# drv8353_based_bldc_power_stage.net
KiCad netlist of a schematic drawn in EAGLE
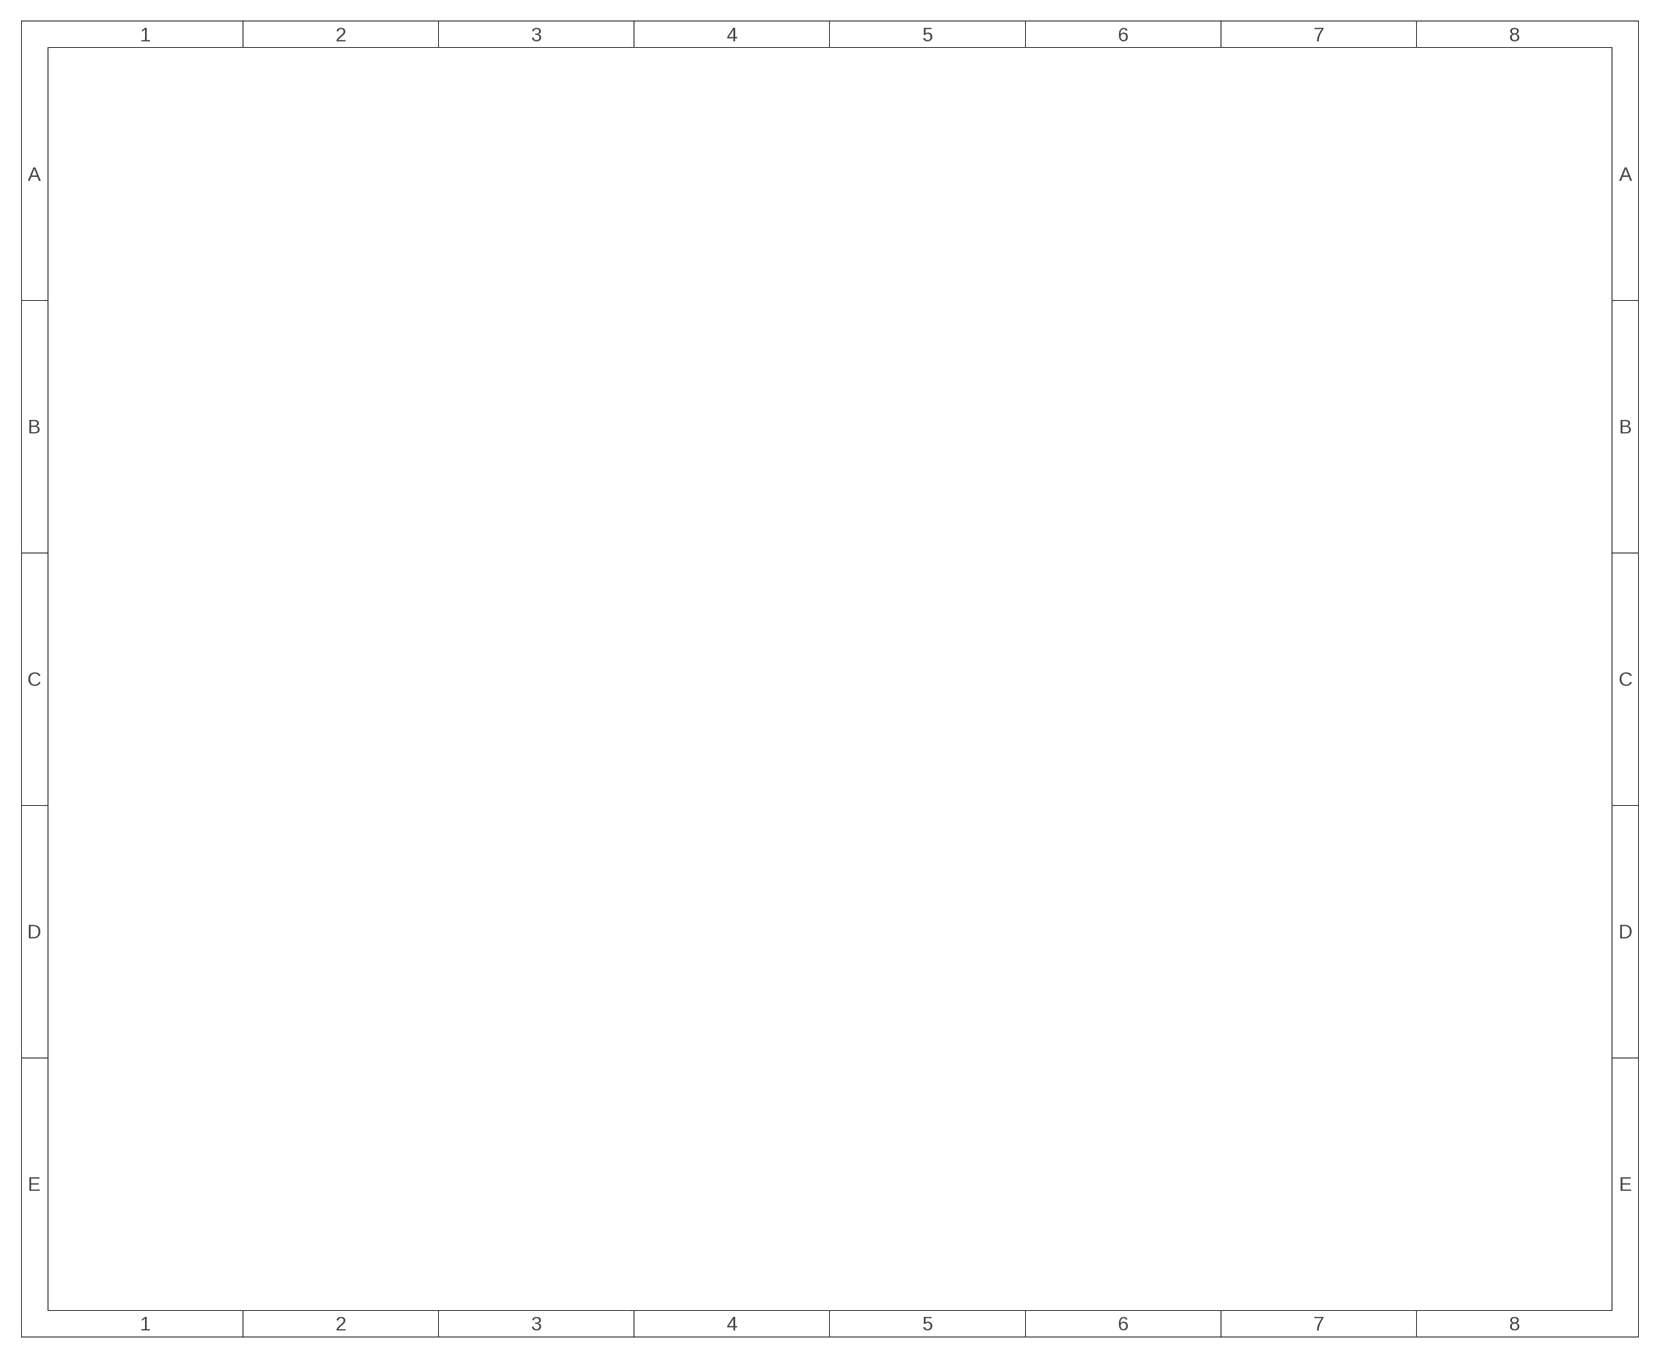
[diagram p0: schematic, sheet 1]
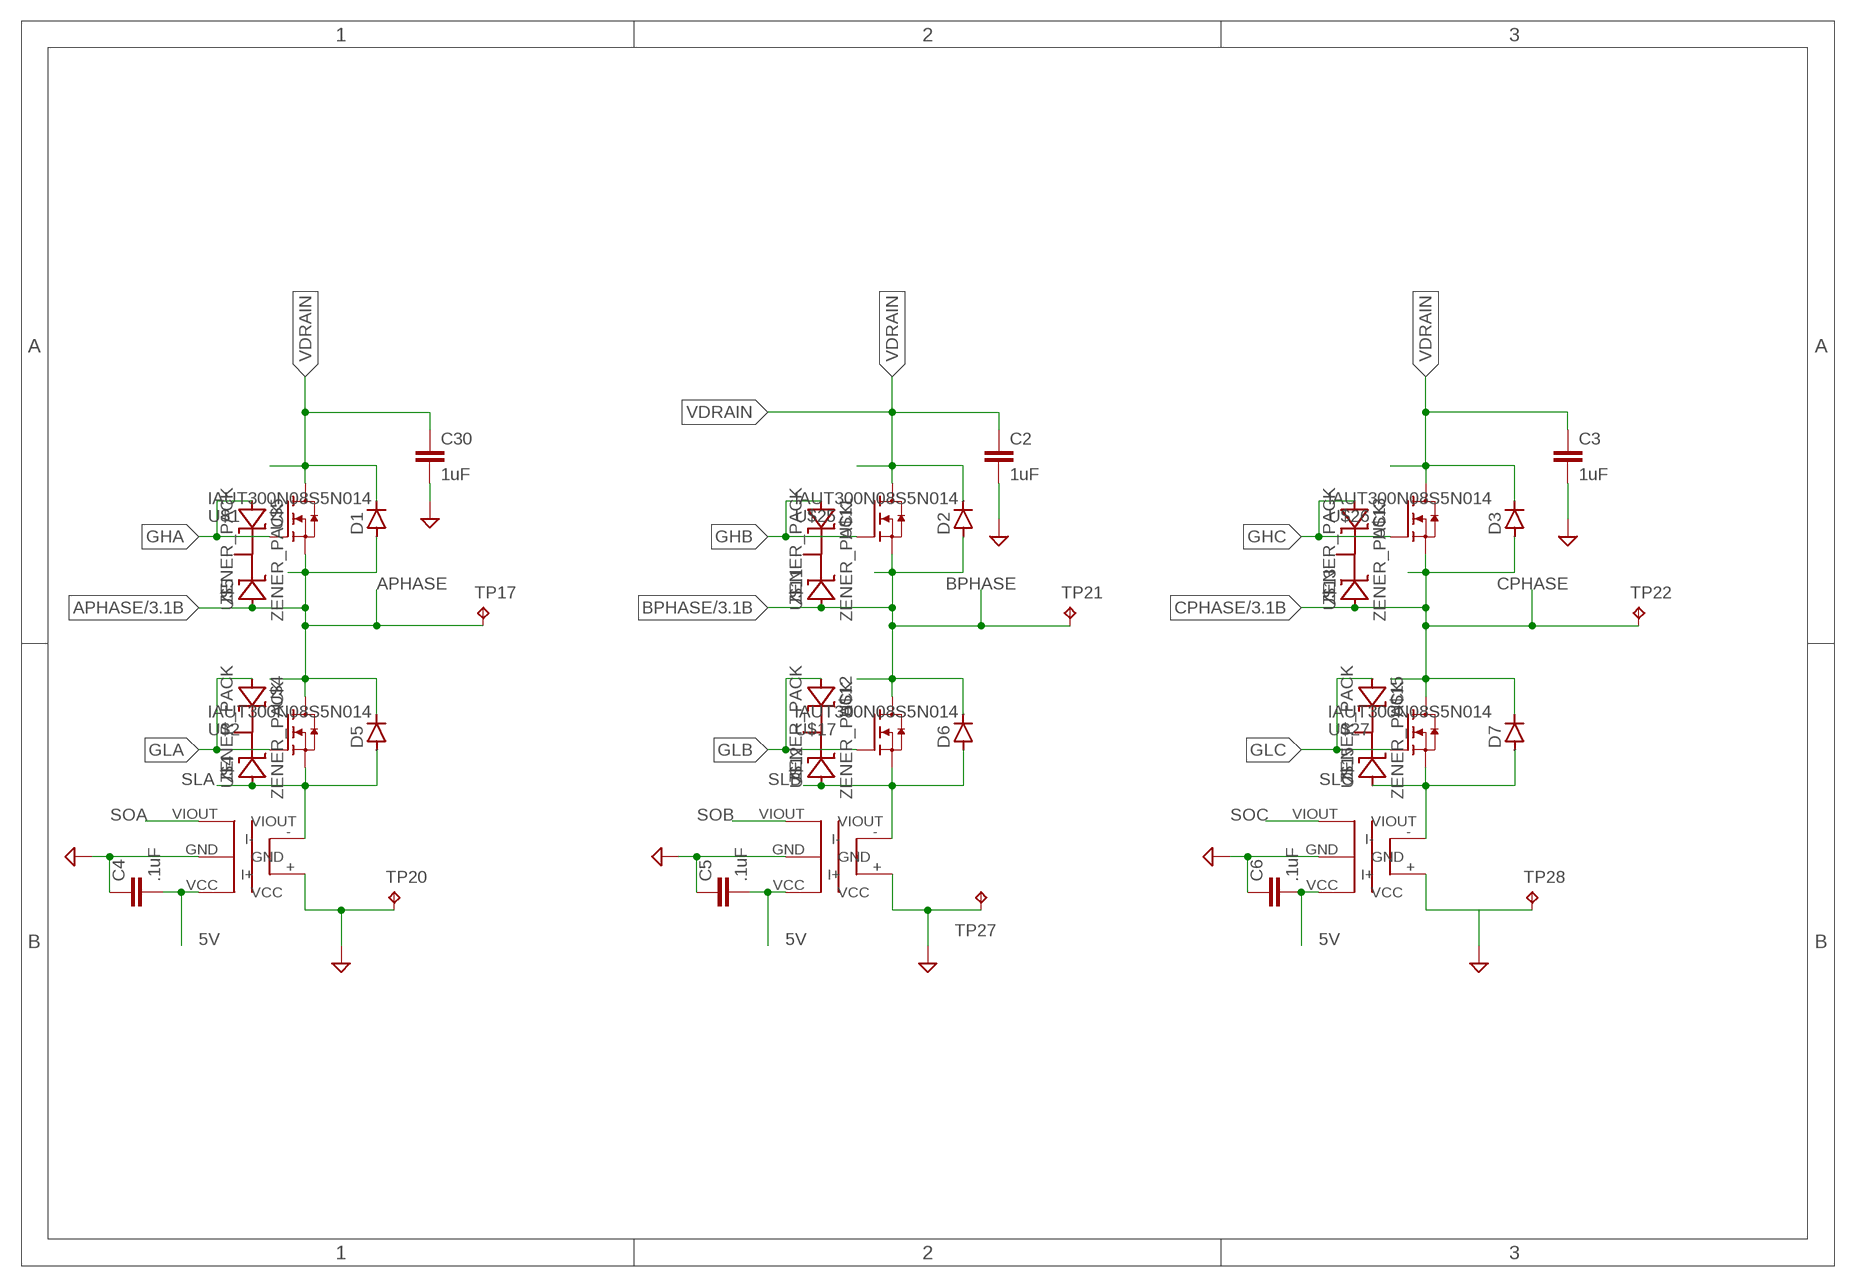
[diagram p1: schematic, sheet 2]
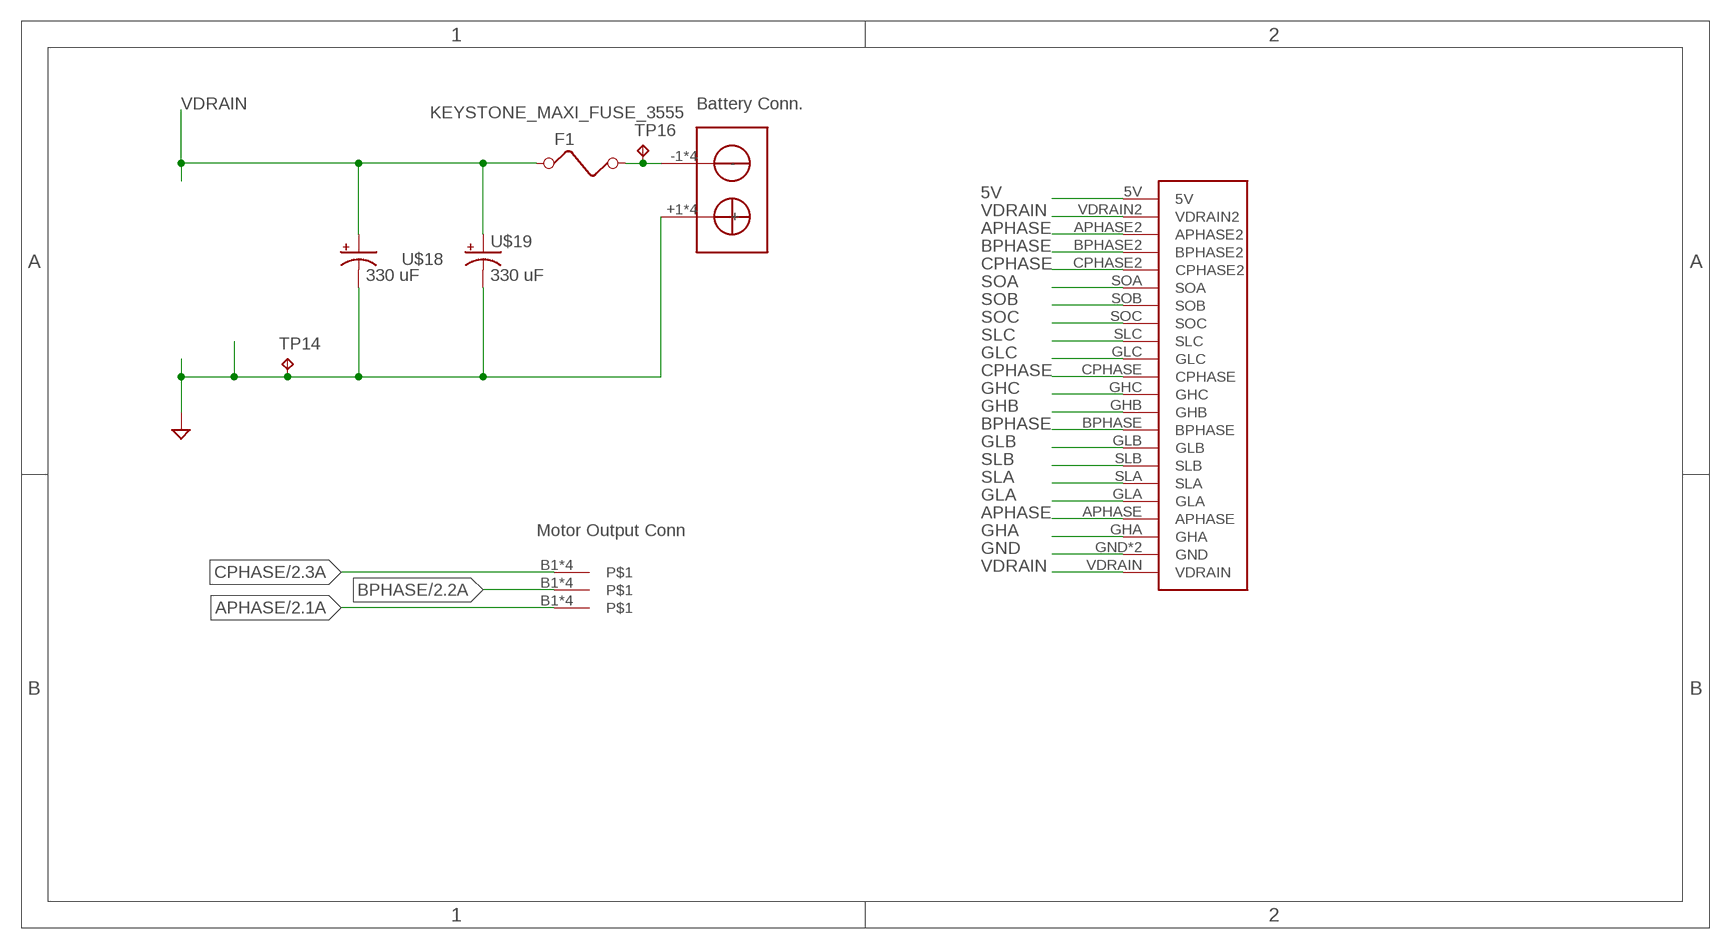
[diagram p2: schematic, sheet 3]

(export (version "E")
  (design (tool "Eeschema 10.0.6"))
  (components
    (comp (ref "C2")
      (value "1uF")
      (footprint "eagle-import:C1206")
      (libsource (lib "eagle-import") (part "C-EUC1206"))
    )
    (comp (ref "C3")
      (value "1uF")
      (footprint "eagle-import:C1206")
      (libsource (lib "eagle-import") (part "C-EUC1206"))
    )
    (comp (ref "C4")
      (value ".1uF")
      (footprint "eagle-import:C0603K")
      (libsource (lib "eagle-import") (part "C-EUC0603K"))
    )
    (comp (ref "C5")
      (value ".1uF")
      (footprint "eagle-import:C0603K")
      (libsource (lib "eagle-import") (part "C-EUC0603K"))
    )
    (comp (ref "C6")
      (value ".1uF")
      (footprint "eagle-import:C0603K")
      (libsource (lib "eagle-import") (part "C-EUC0603K"))
    )
    (comp (ref "C30")
      (value "1uF")
      (footprint "eagle-import:C1206")
      (libsource (lib "eagle-import") (part "C-EUC1206"))
    )
    (comp (ref "D1")
      (value "D-SOD123")
      (footprint "eagle-import:SOD123")
      (libsource (lib "eagle-import") (part "D-SOD123"))
    )
    (comp (ref "D2")
      (value "D-SOD123")
      (footprint "eagle-import:SOD123")
      (libsource (lib "eagle-import") (part "D-SOD123"))
    )
    (comp (ref "D3")
      (value "D-SOD123")
      (footprint "eagle-import:SOD123")
      (libsource (lib "eagle-import") (part "D-SOD123"))
    )
    (comp (ref "D5")
      (value "D-SOD123")
      (footprint "eagle-import:SOD123")
      (libsource (lib "eagle-import") (part "D-SOD123"))
    )
    (comp (ref "D6")
      (value "D-SOD123")
      (footprint "eagle-import:SOD123")
      (libsource (lib "eagle-import") (part "D-SOD123"))
    )
    (comp (ref "D7")
      (value "D-SOD123")
      (footprint "eagle-import:SOD123")
      (libsource (lib "eagle-import") (part "D-SOD123"))
    )
    (comp (ref "TP17")
      (value "TPB1,27")
      (footprint "eagle-import:B1,27")
      (libsource (lib "eagle-import") (part "TPB1,27"))
    )
    (comp (ref "TP20")
      (value "TPB1,27")
      (footprint "eagle-import:B1,27")
      (libsource (lib "eagle-import") (part "TPB1,27"))
    )
    (comp (ref "TP21")
      (value "TPB1,27")
      (footprint "eagle-import:B1,27")
      (libsource (lib "eagle-import") (part "TPB1,27"))
    )
    (comp (ref "TP22")
      (value "TPB1,27")
      (footprint "eagle-import:B1,27")
      (libsource (lib "eagle-import") (part "TPB1,27"))
    )
    (comp (ref "TP27")
      (value "TPB1,27")
      (footprint "eagle-import:B1,27")
      (libsource (lib "eagle-import") (part "TPB1,27"))
    )
    (comp (ref "TP28")
      (value "TPB1,27")
      (footprint "eagle-import:B1,27")
      (libsource (lib "eagle-import") (part "TPB1,27"))
    )
    (comp (ref "U$1")
      (value "IAUT300N08S5N014")
      (footprint "eagle-import:PG-HSOF-8-1_MODIFIED")
      (libsource (lib "eagle-import") (part "IAUT300N08S5N014"))
    )
    (comp (ref "U$2")
      (value "IAUT300N08S5N014")
      (footprint "eagle-import:PG-HSOF-8-1_MODIFIED")
      (libsource (lib "eagle-import") (part "IAUT300N08S5N014"))
    )
    (comp (ref "U$3")
      (value "ACS770LCB-050B-PFF-T")
      (footprint "eagle-import:LEADFORM_PFF")
      (libsource (lib "eagle-import") (part "ACS770LCB-050B-PFF-T"))
    )
    (comp (ref "U$4")
      (value "ZENER_PACK")
      (footprint "eagle-import:SOT23")
      (libsource (lib "eagle-import") (part "ZENER_PACK"))
    )
    (comp (ref "U$5")
      (value "ZENER_PACK")
      (footprint "eagle-import:SOT23")
      (libsource (lib "eagle-import") (part "ZENER_PACK"))
    )
    (comp (ref "U$9")
      (value "ACS770LCB-050B-PFF-T")
      (footprint "eagle-import:LEADFORM_PFF")
      (libsource (lib "eagle-import") (part "ACS770LCB-050B-PFF-T"))
    )
    (comp (ref "U$10")
      (value "ACS770LCB-050B-PFF-T")
      (footprint "eagle-import:LEADFORM_PFF")
      (libsource (lib "eagle-import") (part "ACS770LCB-050B-PFF-T"))
    )
    (comp (ref "U$11")
      (value "ZENER_PACK")
      (footprint "eagle-import:SOT23")
      (libsource (lib "eagle-import") (part "ZENER_PACK"))
    )
    (comp (ref "U$12")
      (value "ZENER_PACK")
      (footprint "eagle-import:SOT23")
      (libsource (lib "eagle-import") (part "ZENER_PACK"))
    )
    (comp (ref "U$13")
      (value "ZENER_PACK")
      (footprint "eagle-import:SOT23")
      (libsource (lib "eagle-import") (part "ZENER_PACK"))
    )
    (comp (ref "U$15")
      (value "ZENER_PACK")
      (footprint "eagle-import:SOT23")
      (libsource (lib "eagle-import") (part "ZENER_PACK"))
    )
    (comp (ref "U$17")
      (value "IAUT300N08S5N014")
      (footprint "eagle-import:PG-HSOF-8-1_MODIFIED")
      (libsource (lib "eagle-import") (part "IAUT300N08S5N014"))
    )
    (comp (ref "U$25")
      (value "IAUT300N08S5N014")
      (footprint "eagle-import:PG-HSOF-8-1_MODIFIED")
      (libsource (lib "eagle-import") (part "IAUT300N08S5N014"))
    )
    (comp (ref "U$26")
      (value "IAUT300N08S5N014")
      (footprint "eagle-import:PG-HSOF-8-1_MODIFIED")
      (libsource (lib "eagle-import") (part "IAUT300N08S5N014"))
    )
    (comp (ref "U$27")
      (value "IAUT300N08S5N014")
      (footprint "eagle-import:PG-HSOF-8-1_MODIFIED")
      (libsource (lib "eagle-import") (part "IAUT300N08S5N014"))
    )
    (comp (ref "F1")
      (value "KEYSTONE_MAXI_FUSE_3555")
      (footprint "eagle-import:KEYSTONE_MAXI_FUSE_CLIP_3555")
      (libsource (lib "eagle-import") (part "KEYSTONE_MAXI_FUSE_3555"))
    )
    (comp (ref "TP14")
      (value "TPB1,27")
      (footprint "eagle-import:B1,27")
      (libsource (lib "eagle-import") (part "TPB1,27"))
    )
    (comp (ref "TP16")
      (value "TPB1,27")
      (footprint "eagle-import:B1,27")
      (libsource (lib "eagle-import") (part "TPB1,27"))
    )
    (comp (ref "U$6")
      (value "MINI-PP75")
      (footprint "eagle-import:MINI-PP75")
      (libsource (lib "eagle-import") (part "MINI-PP75"))
    )
    (comp (ref "U$7")
      (value "MINI-PP75")
      (footprint "eagle-import:MINI-PP75")
      (libsource (lib "eagle-import") (part "MINI-PP75"))
    )
    (comp (ref "U$8")
      (value "MINI-PP75")
      (footprint "eagle-import:MINI-PP75")
      (libsource (lib "eagle-import") (part "MINI-PP75"))
    )
    (comp (ref "U$14")
      (value "POWER_STAGE_CONNECTOR")
      (footprint "eagle-import:POWER_STAGE_CONNECTION")
      (libsource (lib "eagle-import") (part "POWER_STAGE_CONNECTOR"))
    )
    (comp (ref "U$16")
      (value "SB50")
      (footprint "eagle-import:MINI-SB-50")
      (libsource (lib "eagle-import") (part "SB50"))
    )
    (comp (ref "U$18")
      (value "330 uF")
      (footprint "eagle-import:SM_RADIAL_K16_1PRIMARY")
      (libsource (lib "eagle-import") (part "RADIALK16"))
    )
    (comp (ref "U$19")
      (value "330 uF")
      (footprint "eagle-import:SM_RADIAL_K16_1PRIMARY")
      (libsource (lib "eagle-import") (part "RADIALK16"))
    )
  )
  (nets
    (net (code "1") (name "5V") (class "Default")
      (node (ref "C4") (pin "2") (pinfunction "2_2") (pintype "passive"))
      (node (ref "C5") (pin "2") (pinfunction "2_2") (pintype "passive"))
      (node (ref "C6") (pin "2") (pinfunction "2_2") (pintype "passive"))
      (node (ref "U$10") (pin "VCC") (pinfunction "VCC_VCC") (pintype "bidirectional"))
      (node (ref "U$14") (pin "5V") (pinfunction "5V_5V") (pintype "bidirectional"))
      (node (ref "U$3") (pin "VCC") (pinfunction "VCC_VCC") (pintype "bidirectional"))
      (node (ref "U$9") (pin "VCC") (pinfunction "VCC_VCC") (pintype "bidirectional"))
    )
    (net (code "2") (name "APHASE") (class "Default")
      (node (ref "D1") (pin "2") (pinfunction "A_2") (pintype "passive"))
      (node (ref "D5") (pin "LINE") (pinfunction "C_LINE") (pintype "passive"))
      (node (ref "TP17") (pin "TP") (pinfunction "TP_TP") (pintype "input"))
      (node (ref "U$1") (pin "10") (pinfunction "S_10") (pintype "passive"))
      (node (ref "U$1") (pin "11") (pinfunction "S_11") (pintype "passive"))
      (node (ref "U$1") (pin "12") (pinfunction "S_12") (pintype "passive"))
      (node (ref "U$1") (pin "13") (pinfunction "S_13") (pintype "passive"))
      (node (ref "U$1") (pin "14") (pinfunction "S_14") (pintype "passive"))
      (node (ref "U$1") (pin "15") (pinfunction "S_15") (pintype "passive"))
      (node (ref "U$1") (pin "2") (pinfunction "S_2") (pintype "passive"))
      (node (ref "U$1") (pin "3") (pinfunction "S_3") (pintype "passive"))
      (node (ref "U$1") (pin "4") (pinfunction "S_4") (pintype "passive"))
      (node (ref "U$1") (pin "5") (pinfunction "S_5") (pintype "passive"))
      (node (ref "U$1") (pin "6") (pinfunction "S_6") (pintype "passive"))
      (node (ref "U$1") (pin "7") (pinfunction "S_7") (pintype "passive"))
      (node (ref "U$1") (pin "8") (pinfunction "S_8") (pintype "passive"))
      (node (ref "U$14") (pin "APHASE") (pinfunction "APHASE_APHASE") (pintype "bidirectional"))
      (node (ref "U$14") (pin "APHASE2") (pinfunction "APHASE2_APHASE2") (pintype "bidirectional"))
      (node (ref "U$2") (pin "16") (pinfunction "D_16") (pintype "passive"))
      (node (ref "U$2") (pin "17") (pinfunction "D_17") (pintype "passive"))
      (node (ref "U$2") (pin "18") (pinfunction "D_18") (pintype "passive"))
      (node (ref "U$2") (pin "19") (pinfunction "D_19") (pintype "passive"))
      (node (ref "U$2") (pin "9") (pinfunction "D_9") (pintype "passive"))
      (node (ref "U$5") (pin "1") (pinfunction "END1_1") (pintype "passive"))
      (node (ref "U$8") (pin "B1") (pinfunction "P$1_B1") (pintype "bidirectional"))
      (node (ref "U$8") (pin "B2") (pinfunction "P$1_B2") (pintype "bidirectional"))
      (node (ref "U$8") (pin "B3") (pinfunction "P$1_B3") (pintype "bidirectional"))
      (node (ref "U$8") (pin "B4") (pinfunction "P$1_B4") (pintype "bidirectional"))
    )
    (net (code "3") (name "BPHASE") (class "Default")
      (node (ref "D2") (pin "2") (pinfunction "A_2") (pintype "passive"))
      (node (ref "D6") (pin "LINE") (pinfunction "C_LINE") (pintype "passive"))
      (node (ref "TP21") (pin "TP") (pinfunction "TP_TP") (pintype "input"))
      (node (ref "U$11") (pin "1") (pinfunction "END1_1") (pintype "passive"))
      (node (ref "U$14") (pin "BPHASE") (pinfunction "BPHASE_BPHASE") (pintype "bidirectional"))
      (node (ref "U$14") (pin "BPHASE2") (pinfunction "BPHASE2_BPHASE2") (pintype "bidirectional"))
      (node (ref "U$17") (pin "16") (pinfunction "D_16") (pintype "passive"))
      (node (ref "U$17") (pin "17") (pinfunction "D_17") (pintype "passive"))
      (node (ref "U$17") (pin "18") (pinfunction "D_18") (pintype "passive"))
      (node (ref "U$17") (pin "19") (pinfunction "D_19") (pintype "passive"))
      (node (ref "U$17") (pin "9") (pinfunction "D_9") (pintype "passive"))
      (node (ref "U$25") (pin "10") (pinfunction "S_10") (pintype "passive"))
      (node (ref "U$25") (pin "11") (pinfunction "S_11") (pintype "passive"))
      (node (ref "U$25") (pin "12") (pinfunction "S_12") (pintype "passive"))
      (node (ref "U$25") (pin "13") (pinfunction "S_13") (pintype "passive"))
      (node (ref "U$25") (pin "14") (pinfunction "S_14") (pintype "passive"))
      (node (ref "U$25") (pin "15") (pinfunction "S_15") (pintype "passive"))
      (node (ref "U$25") (pin "2") (pinfunction "S_2") (pintype "passive"))
      (node (ref "U$25") (pin "3") (pinfunction "S_3") (pintype "passive"))
      (node (ref "U$25") (pin "4") (pinfunction "S_4") (pintype "passive"))
      (node (ref "U$25") (pin "5") (pinfunction "S_5") (pintype "passive"))
      (node (ref "U$25") (pin "6") (pinfunction "S_6") (pintype "passive"))
      (node (ref "U$25") (pin "7") (pinfunction "S_7") (pintype "passive"))
      (node (ref "U$25") (pin "8") (pinfunction "S_8") (pintype "passive"))
      (node (ref "U$7") (pin "B1") (pinfunction "P$1_B1") (pintype "bidirectional"))
      (node (ref "U$7") (pin "B2") (pinfunction "P$1_B2") (pintype "bidirectional"))
      (node (ref "U$7") (pin "B3") (pinfunction "P$1_B3") (pintype "bidirectional"))
      (node (ref "U$7") (pin "B4") (pinfunction "P$1_B4") (pintype "bidirectional"))
    )
    (net (code "4") (name "CPHASE") (class "Default")
      (node (ref "D3") (pin "2") (pinfunction "A_2") (pintype "passive"))
      (node (ref "D7") (pin "LINE") (pinfunction "C_LINE") (pintype "passive"))
      (node (ref "TP22") (pin "TP") (pinfunction "TP_TP") (pintype "input"))
      (node (ref "U$13") (pin "1") (pinfunction "END1_1") (pintype "passive"))
      (node (ref "U$14") (pin "CPHASE") (pinfunction "CPHASE_CPHASE") (pintype "bidirectional"))
      (node (ref "U$14") (pin "CPHASE2") (pinfunction "CPHASE2_CPHASE2") (pintype "bidirectional"))
      (node (ref "U$26") (pin "10") (pinfunction "S_10") (pintype "passive"))
      (node (ref "U$26") (pin "11") (pinfunction "S_11") (pintype "passive"))
      (node (ref "U$26") (pin "12") (pinfunction "S_12") (pintype "passive"))
      (node (ref "U$26") (pin "13") (pinfunction "S_13") (pintype "passive"))
      (node (ref "U$26") (pin "14") (pinfunction "S_14") (pintype "passive"))
      (node (ref "U$26") (pin "15") (pinfunction "S_15") (pintype "passive"))
      (node (ref "U$26") (pin "2") (pinfunction "S_2") (pintype "passive"))
      (node (ref "U$26") (pin "3") (pinfunction "S_3") (pintype "passive"))
      (node (ref "U$26") (pin "4") (pinfunction "S_4") (pintype "passive"))
      (node (ref "U$26") (pin "5") (pinfunction "S_5") (pintype "passive"))
      (node (ref "U$26") (pin "6") (pinfunction "S_6") (pintype "passive"))
      (node (ref "U$26") (pin "7") (pinfunction "S_7") (pintype "passive"))
      (node (ref "U$26") (pin "8") (pinfunction "S_8") (pintype "passive"))
      (node (ref "U$27") (pin "16") (pinfunction "D_16") (pintype "passive"))
      (node (ref "U$27") (pin "17") (pinfunction "D_17") (pintype "passive"))
      (node (ref "U$27") (pin "18") (pinfunction "D_18") (pintype "passive"))
      (node (ref "U$27") (pin "19") (pinfunction "D_19") (pintype "passive"))
      (node (ref "U$27") (pin "9") (pinfunction "D_9") (pintype "passive"))
      (node (ref "U$6") (pin "B1") (pinfunction "P$1_B1") (pintype "bidirectional"))
      (node (ref "U$6") (pin "B2") (pinfunction "P$1_B2") (pintype "bidirectional"))
      (node (ref "U$6") (pin "B3") (pinfunction "P$1_B3") (pintype "bidirectional"))
      (node (ref "U$6") (pin "B4") (pinfunction "P$1_B4") (pintype "bidirectional"))
    )
    (net (code "5") (name "GHA") (class "Default")
      (node (ref "U$1") (pin "1") (pinfunction "G_1") (pintype "passive"))
      (node (ref "U$14") (pin "GHA") (pinfunction "GHA_GHA") (pintype "bidirectional"))
      (node (ref "U$5") (pin "2") (pinfunction "END2_2") (pintype "passive"))
    )
    (net (code "6") (name "GHB") (class "Default")
      (node (ref "U$11") (pin "2") (pinfunction "END2_2") (pintype "passive"))
      (node (ref "U$14") (pin "GHB") (pinfunction "GHB_GHB") (pintype "bidirectional"))
      (node (ref "U$25") (pin "1") (pinfunction "G_1") (pintype "passive"))
    )
    (net (code "7") (name "GHC") (class "Default")
      (node (ref "U$13") (pin "2") (pinfunction "END2_2") (pintype "passive"))
      (node (ref "U$14") (pin "GHC") (pinfunction "GHC_GHC") (pintype "bidirectional"))
      (node (ref "U$26") (pin "1") (pinfunction "G_1") (pintype "passive"))
    )
    (net (code "8") (name "GLA") (class "Default")
      (node (ref "U$14") (pin "GLA") (pinfunction "GLA_GLA") (pintype "bidirectional"))
      (node (ref "U$2") (pin "1") (pinfunction "G_1") (pintype "passive"))
      (node (ref "U$4") (pin "2") (pinfunction "END2_2") (pintype "passive"))
    )
    (net (code "9") (name "GLB") (class "Default")
      (node (ref "U$12") (pin "2") (pinfunction "END2_2") (pintype "passive"))
      (node (ref "U$14") (pin "GLB") (pinfunction "GLB_GLB") (pintype "bidirectional"))
      (node (ref "U$17") (pin "1") (pinfunction "G_1") (pintype "passive"))
    )
    (net (code "10") (name "GLC") (class "Default")
      (node (ref "U$14") (pin "GLC") (pinfunction "GLC_GLC") (pintype "bidirectional"))
      (node (ref "U$15") (pin "2") (pinfunction "END2_2") (pintype "passive"))
      (node (ref "U$27") (pin "1") (pinfunction "G_1") (pintype "passive"))
    )
    (net (code "11") (name "GND") (class "Default")
      (node (ref "C2") (pin "2") (pinfunction "2_2") (pintype "passive"))
      (node (ref "C3") (pin "2") (pinfunction "2_2") (pintype "passive"))
      (node (ref "C30") (pin "2") (pinfunction "2_2") (pintype "passive"))
      (node (ref "C4") (pin "1") (pinfunction "1_1") (pintype "passive"))
      (node (ref "C5") (pin "1") (pinfunction "1_1") (pintype "passive"))
      (node (ref "C6") (pin "1") (pinfunction "1_1") (pintype "passive"))
      (node (ref "TP14") (pin "TP") (pinfunction "TP_TP") (pintype "input"))
      (node (ref "TP20") (pin "TP") (pinfunction "TP_TP") (pintype "input"))
      (node (ref "TP27") (pin "TP") (pinfunction "TP_TP") (pintype "input"))
      (node (ref "TP28") (pin "TP") (pinfunction "TP_TP") (pintype "input"))
      (node (ref "U$10") (pin "+") (pinfunction "I+_+") (pintype "bidirectional"))
      (node (ref "U$10") (pin "GND") (pinfunction "GND_GND") (pintype "bidirectional"))
      (node (ref "U$14") (pin "GND") (pinfunction "GND_GND") (pintype "bidirectional"))
      (node (ref "U$14") (pin "GND2") (pinfunction "GND_GND2") (pintype "bidirectional"))
      (node (ref "U$16") (pin "+1") (pinfunction "+_+1") (pintype "bidirectional"))
      (node (ref "U$16") (pin "+2") (pinfunction "+_+2") (pintype "bidirectional"))
      (node (ref "U$16") (pin "+3") (pinfunction "+_+3") (pintype "bidirectional"))
      (node (ref "U$16") (pin "+4") (pinfunction "+_+4") (pintype "bidirectional"))
      (node (ref "U$18") (pin "-") (pinfunction "-_-") (pintype "passive"))
      (node (ref "U$19") (pin "-") (pinfunction "-_-") (pintype "passive"))
      (node (ref "U$3") (pin "+") (pinfunction "I+_+") (pintype "bidirectional"))
      (node (ref "U$3") (pin "GND") (pinfunction "GND_GND") (pintype "bidirectional"))
      (node (ref "U$9") (pin "+") (pinfunction "I+_+") (pintype "bidirectional"))
      (node (ref "U$9") (pin "GND") (pinfunction "GND_GND") (pintype "bidirectional"))
    )
    (net (code "12") (name "Net-(F1-2-PadB1)") (class "Default")
      (node (ref "F1") (pin "B1") (pinfunction "2_B1") (pintype "passive"))
      (node (ref "F1") (pin "B2") (pinfunction "2_B2") (pintype "passive"))
      (node (ref "TP16") (pin "TP") (pinfunction "TP_TP") (pintype "input"))
      (node (ref "U$16") (pin "-1") (pinfunction "-_-1") (pintype "bidirectional"))
      (node (ref "U$16") (pin "-2") (pinfunction "-_-2") (pintype "bidirectional"))
      (node (ref "U$16") (pin "-3") (pinfunction "-_-3") (pintype "bidirectional"))
      (node (ref "U$16") (pin "-4") (pinfunction "-_-4") (pintype "bidirectional"))
    )
    (net (code "13") (name "SLA") (class "Default")
      (node (ref "D5") (pin "2") (pinfunction "A_2") (pintype "passive"))
      (node (ref "U$14") (pin "SLA") (pinfunction "SLA_SLA") (pintype "bidirectional"))
      (node (ref "U$2") (pin "10") (pinfunction "S_10") (pintype "passive"))
      (node (ref "U$2") (pin "11") (pinfunction "S_11") (pintype "passive"))
      (node (ref "U$2") (pin "12") (pinfunction "S_12") (pintype "passive"))
      (node (ref "U$2") (pin "13") (pinfunction "S_13") (pintype "passive"))
      (node (ref "U$2") (pin "14") (pinfunction "S_14") (pintype "passive"))
      (node (ref "U$2") (pin "15") (pinfunction "S_15") (pintype "passive"))
      (node (ref "U$2") (pin "2") (pinfunction "S_2") (pintype "passive"))
      (node (ref "U$2") (pin "3") (pinfunction "S_3") (pintype "passive"))
      (node (ref "U$2") (pin "4") (pinfunction "S_4") (pintype "passive"))
      (node (ref "U$2") (pin "5") (pinfunction "S_5") (pintype "passive"))
      (node (ref "U$2") (pin "6") (pinfunction "S_6") (pintype "passive"))
      (node (ref "U$2") (pin "7") (pinfunction "S_7") (pintype "passive"))
      (node (ref "U$2") (pin "8") (pinfunction "S_8") (pintype "passive"))
      (node (ref "U$3") (pin "-") (pinfunction "I-_-") (pintype "bidirectional"))
      (node (ref "U$4") (pin "1") (pinfunction "END1_1") (pintype "passive"))
    )
    (net (code "14") (name "SLB") (class "Default")
      (node (ref "D6") (pin "2") (pinfunction "A_2") (pintype "passive"))
      (node (ref "U$12") (pin "1") (pinfunction "END1_1") (pintype "passive"))
      (node (ref "U$14") (pin "SLB") (pinfunction "SLB_SLB") (pintype "bidirectional"))
      (node (ref "U$17") (pin "10") (pinfunction "S_10") (pintype "passive"))
      (node (ref "U$17") (pin "11") (pinfunction "S_11") (pintype "passive"))
      (node (ref "U$17") (pin "12") (pinfunction "S_12") (pintype "passive"))
      (node (ref "U$17") (pin "13") (pinfunction "S_13") (pintype "passive"))
      (node (ref "U$17") (pin "14") (pinfunction "S_14") (pintype "passive"))
      (node (ref "U$17") (pin "15") (pinfunction "S_15") (pintype "passive"))
      (node (ref "U$17") (pin "2") (pinfunction "S_2") (pintype "passive"))
      (node (ref "U$17") (pin "3") (pinfunction "S_3") (pintype "passive"))
      (node (ref "U$17") (pin "4") (pinfunction "S_4") (pintype "passive"))
      (node (ref "U$17") (pin "5") (pinfunction "S_5") (pintype "passive"))
      (node (ref "U$17") (pin "6") (pinfunction "S_6") (pintype "passive"))
      (node (ref "U$17") (pin "7") (pinfunction "S_7") (pintype "passive"))
      (node (ref "U$17") (pin "8") (pinfunction "S_8") (pintype "passive"))
      (node (ref "U$9") (pin "-") (pinfunction "I-_-") (pintype "bidirectional"))
    )
    (net (code "15") (name "SLC") (class "Default")
      (node (ref "D7") (pin "2") (pinfunction "A_2") (pintype "passive"))
      (node (ref "U$10") (pin "-") (pinfunction "I-_-") (pintype "bidirectional"))
      (node (ref "U$14") (pin "SLC") (pinfunction "SLC_SLC") (pintype "bidirectional"))
      (node (ref "U$15") (pin "1") (pinfunction "END1_1") (pintype "passive"))
      (node (ref "U$27") (pin "10") (pinfunction "S_10") (pintype "passive"))
      (node (ref "U$27") (pin "11") (pinfunction "S_11") (pintype "passive"))
      (node (ref "U$27") (pin "12") (pinfunction "S_12") (pintype "passive"))
      (node (ref "U$27") (pin "13") (pinfunction "S_13") (pintype "passive"))
      (node (ref "U$27") (pin "14") (pinfunction "S_14") (pintype "passive"))
      (node (ref "U$27") (pin "15") (pinfunction "S_15") (pintype "passive"))
      (node (ref "U$27") (pin "2") (pinfunction "S_2") (pintype "passive"))
      (node (ref "U$27") (pin "3") (pinfunction "S_3") (pintype "passive"))
      (node (ref "U$27") (pin "4") (pinfunction "S_4") (pintype "passive"))
      (node (ref "U$27") (pin "5") (pinfunction "S_5") (pintype "passive"))
      (node (ref "U$27") (pin "6") (pinfunction "S_6") (pintype "passive"))
      (node (ref "U$27") (pin "7") (pinfunction "S_7") (pintype "passive"))
      (node (ref "U$27") (pin "8") (pinfunction "S_8") (pintype "passive"))
    )
    (net (code "16") (name "SOA") (class "Default")
      (node (ref "U$14") (pin "SOA") (pinfunction "SOA_SOA") (pintype "bidirectional"))
      (node (ref "U$3") (pin "VIOUT") (pinfunction "VIOUT_VIOUT") (pintype "bidirectional"))
    )
    (net (code "17") (name "SOB") (class "Default")
      (node (ref "U$14") (pin "SOB") (pinfunction "SOB_SOB") (pintype "bidirectional"))
      (node (ref "U$9") (pin "VIOUT") (pinfunction "VIOUT_VIOUT") (pintype "bidirectional"))
    )
    (net (code "18") (name "SOC") (class "Default")
      (node (ref "U$10") (pin "VIOUT") (pinfunction "VIOUT_VIOUT") (pintype "bidirectional"))
      (node (ref "U$14") (pin "SOC") (pinfunction "SOC_SOC") (pintype "bidirectional"))
    )
    (net (code "19") (name "VDRAIN") (class "Default")
      (node (ref "C2") (pin "1") (pinfunction "1_1") (pintype "passive"))
      (node (ref "C3") (pin "1") (pinfunction "1_1") (pintype "passive"))
      (node (ref "C30") (pin "1") (pinfunction "1_1") (pintype "passive"))
      (node (ref "D1") (pin "LINE") (pinfunction "C_LINE") (pintype "passive"))
      (node (ref "D2") (pin "LINE") (pinfunction "C_LINE") (pintype "passive"))
      (node (ref "D3") (pin "LINE") (pinfunction "C_LINE") (pintype "passive"))
      (node (ref "F1") (pin "A1") (pinfunction "1_A1") (pintype "passive"))
      (node (ref "F1") (pin "A2") (pinfunction "1_A2") (pintype "passive"))
      (node (ref "U$1") (pin "16") (pinfunction "D_16") (pintype "passive"))
      (node (ref "U$1") (pin "17") (pinfunction "D_17") (pintype "passive"))
      (node (ref "U$1") (pin "18") (pinfunction "D_18") (pintype "passive"))
      (node (ref "U$1") (pin "19") (pinfunction "D_19") (pintype "passive"))
      (node (ref "U$1") (pin "9") (pinfunction "D_9") (pintype "passive"))
      (node (ref "U$14") (pin "VDRAIN") (pinfunction "VDRAIN_VDRAIN") (pintype "bidirectional"))
      (node (ref "U$14") (pin "VDRAIN2") (pinfunction "VDRAIN2_VDRAIN2") (pintype "bidirectional"))
      (node (ref "U$18") (pin "+") (pinfunction "+_+") (pintype "passive"))
      (node (ref "U$19") (pin "+") (pinfunction "+_+") (pintype "passive"))
      (node (ref "U$25") (pin "16") (pinfunction "D_16") (pintype "passive"))
      (node (ref "U$25") (pin "17") (pinfunction "D_17") (pintype "passive"))
      (node (ref "U$25") (pin "18") (pinfunction "D_18") (pintype "passive"))
      (node (ref "U$25") (pin "19") (pinfunction "D_19") (pintype "passive"))
      (node (ref "U$25") (pin "9") (pinfunction "D_9") (pintype "passive"))
      (node (ref "U$26") (pin "16") (pinfunction "D_16") (pintype "passive"))
      (node (ref "U$26") (pin "17") (pinfunction "D_17") (pintype "passive"))
      (node (ref "U$26") (pin "18") (pinfunction "D_18") (pintype "passive"))
      (node (ref "U$26") (pin "19") (pinfunction "D_19") (pintype "passive"))
      (node (ref "U$26") (pin "9") (pinfunction "D_9") (pintype "passive"))
    )
    (net (code "20") (name "unconnected-(U$4-MIDDLE-Pad3)") (class "Default")
      (node (ref "U$4") (pin "3") (pinfunction "MIDDLE_3") (pintype "passive"))
    )
    (net (code "21") (name "unconnected-(U$5-MIDDLE-Pad3)") (class "Default")
      (node (ref "U$5") (pin "3") (pinfunction "MIDDLE_3") (pintype "passive"))
    )
    (net (code "22") (name "unconnected-(U$11-MIDDLE-Pad3)") (class "Default")
      (node (ref "U$11") (pin "3") (pinfunction "MIDDLE_3") (pintype "passive"))
    )
    (net (code "23") (name "unconnected-(U$12-MIDDLE-Pad3)") (class "Default")
      (node (ref "U$12") (pin "3") (pinfunction "MIDDLE_3") (pintype "passive"))
    )
    (net (code "24") (name "unconnected-(U$13-MIDDLE-Pad3)") (class "Default")
      (node (ref "U$13") (pin "3") (pinfunction "MIDDLE_3") (pintype "passive"))
    )
    (net (code "25") (name "unconnected-(U$15-MIDDLE-Pad3)") (class "Default")
      (node (ref "U$15") (pin "3") (pinfunction "MIDDLE_3") (pintype "passive"))
    )
  )
)
